# pwr_misc.net
KiCad netlist of a schematic drawn in Altium Designer
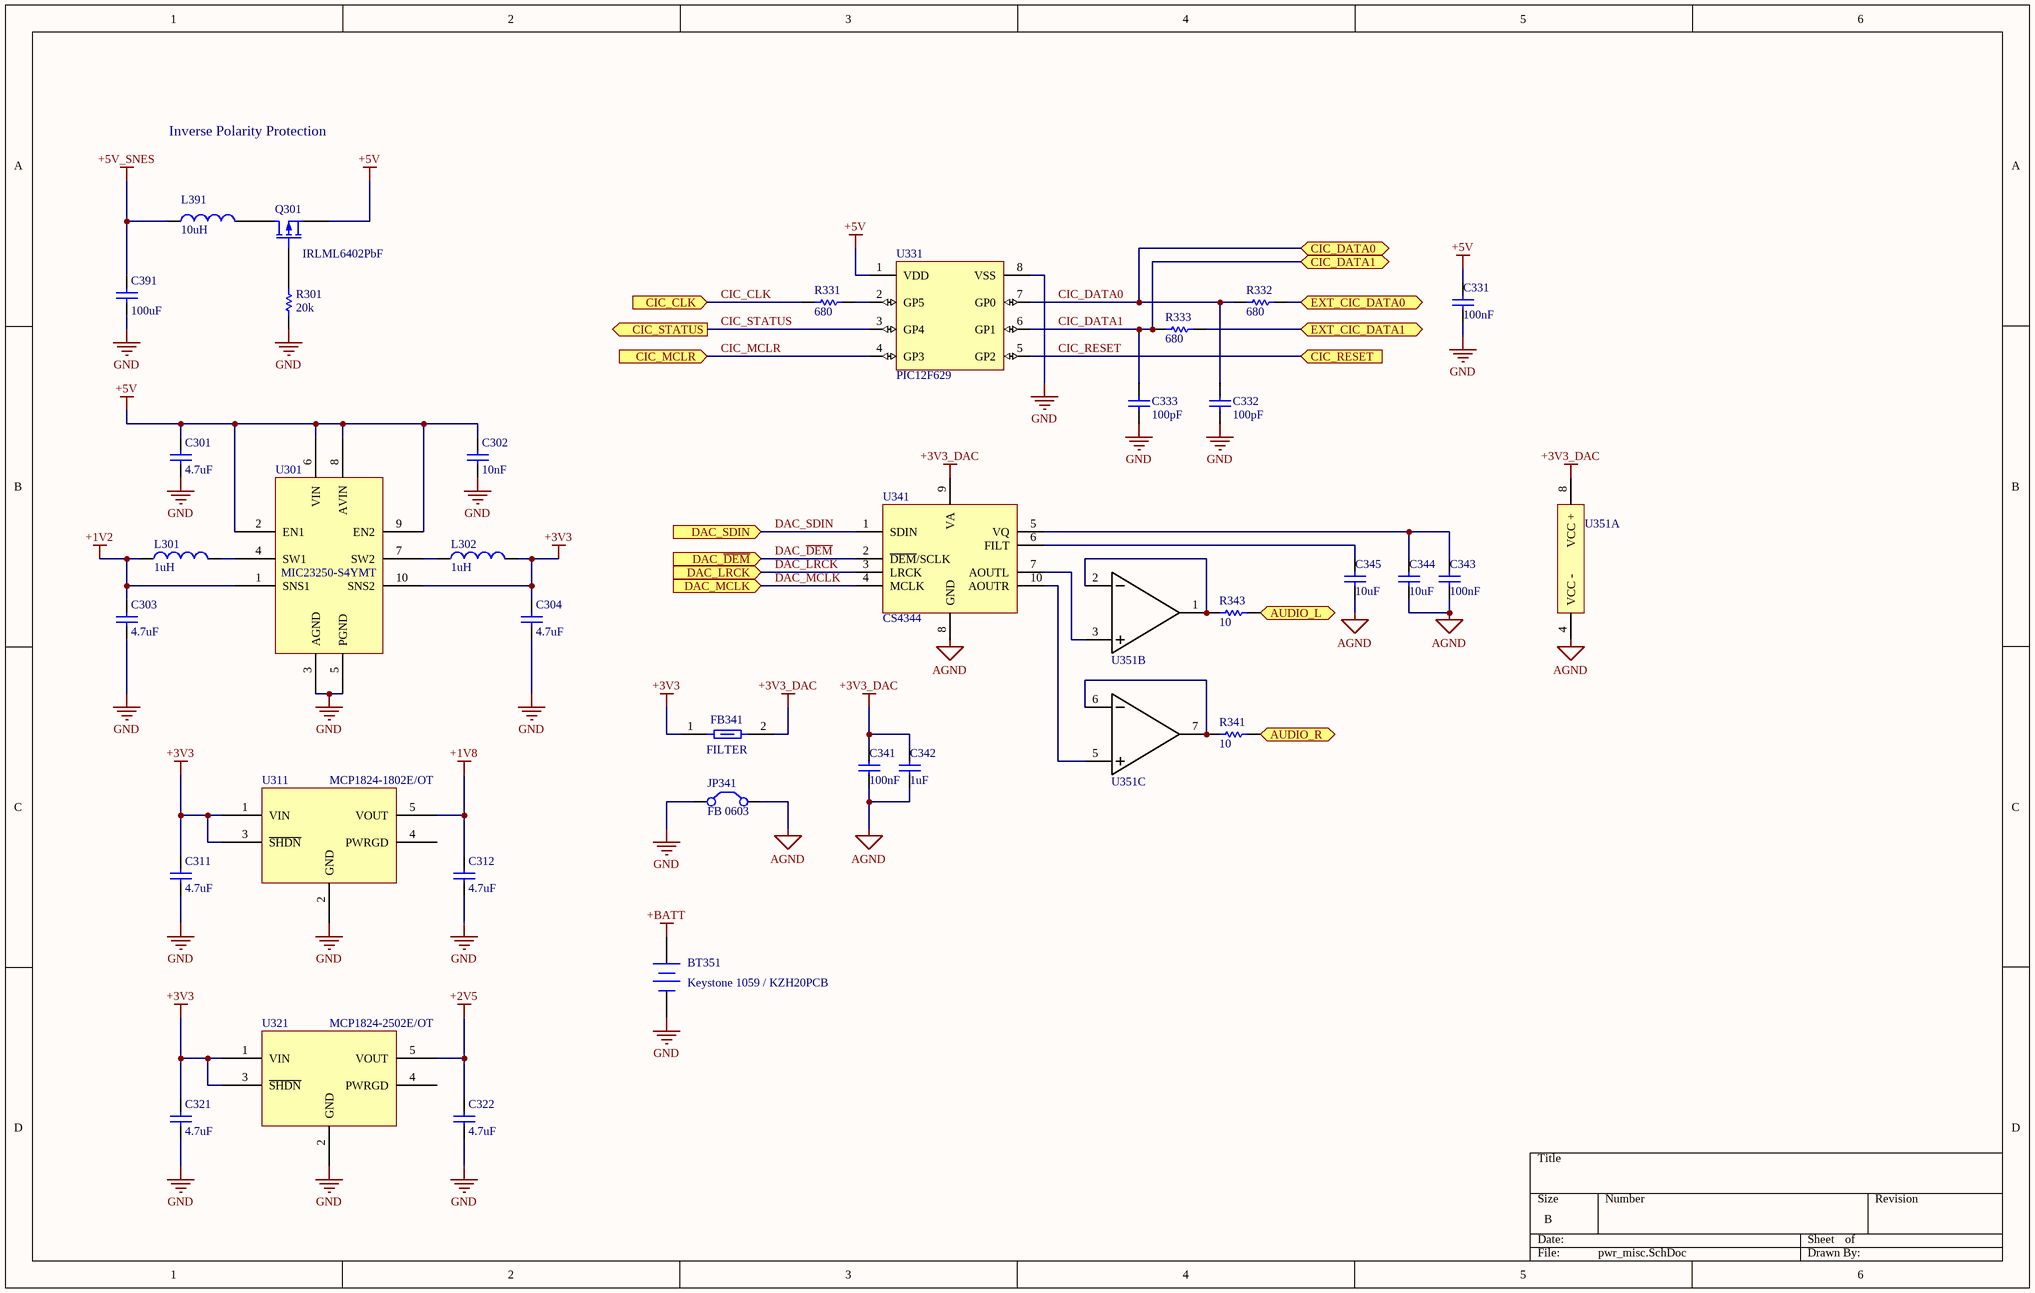
[diagram p0: pwr_misc.SchDoc]

(export (version "E")
  (design (tool "Eeschema 10.0.6"))
  (components
    (comp (ref "BT351")
      (value "Keystone 1059 / KZH20PCB")
      (footprint "BT_KEYSTONE_1059_20MM")
      (description "Battery")
      (libsource (lib "Miscellaneous Devices") (part "Battery"))
    )
    (comp (ref "C301")
      (value "4.7uF")
      (footprint "SM0805")
      (description "Capacitor")
      (libsource (lib "Miscellaneous Devices") (part "Cap"))
    )
    (comp (ref "C302")
      (value "10nF")
      (footprint "SM0805")
      (description "Capacitor")
      (libsource (lib "Miscellaneous Devices") (part "Cap"))
    )
    (comp (ref "C303")
      (value "4.7uF")
      (footprint "SM0805")
      (description "Capacitor")
      (libsource (lib "Miscellaneous Devices") (part "Cap"))
    )
    (comp (ref "C304")
      (value "4.7uF")
      (footprint "SM0805")
      (description "Capacitor")
      (libsource (lib "Miscellaneous Devices") (part "Cap"))
    )
    (comp (ref "C311")
      (value "4.7uF")
      (footprint "SM0805")
      (description "Capacitor")
      (libsource (lib "Miscellaneous Devices") (part "Cap"))
    )
    (comp (ref "C312")
      (value "4.7uF")
      (footprint "SM0805")
      (description "Capacitor")
      (libsource (lib "Miscellaneous Devices") (part "Cap"))
    )
    (comp (ref "C321")
      (value "4.7uF")
      (footprint "SM0805")
      (description "Capacitor")
      (libsource (lib "Miscellaneous Devices") (part "Cap"))
    )
    (comp (ref "C322")
      (value "4.7uF")
      (footprint "SM0805")
      (description "Capacitor")
      (libsource (lib "Miscellaneous Devices") (part "Cap"))
    )
    (comp (ref "C331")
      (value "100nF")
      (footprint "SM0805")
      (description "Capacitor")
      (libsource (lib "Miscellaneous Devices") (part "Cap"))
    )
    (comp (ref "C332")
      (value "100pF")
      (footprint "SM0805")
      (description "Capacitor")
      (libsource (lib "Miscellaneous Devices") (part "Cap"))
    )
    (comp (ref "C333")
      (value "100pF")
      (footprint "SM0805")
      (description "Capacitor")
      (libsource (lib "Miscellaneous Devices") (part "Cap"))
    )
    (comp (ref "C341")
      (value "100nF")
      (footprint "SM0805")
      (description "Capacitor")
      (libsource (lib "Miscellaneous Devices") (part "Cap"))
    )
    (comp (ref "C342")
      (value "1uF")
      (footprint "SM0805")
      (description "Capacitor")
      (libsource (lib "Miscellaneous Devices") (part "Cap"))
    )
    (comp (ref "C343")
      (value "100nF")
      (footprint "SM0805")
      (description "Capacitor")
      (libsource (lib "Miscellaneous Devices") (part "Cap"))
    )
    (comp (ref "C344")
      (value "10uF")
      (footprint "SM0805")
      (description "Capacitor")
      (libsource (lib "Miscellaneous Devices") (part "Cap"))
    )
    (comp (ref "C345")
      (value "10uF")
      (footprint "SM0805")
      (description "Capacitor")
      (libsource (lib "Miscellaneous Devices") (part "Cap"))
    )
    (comp (ref "C391")
      (value "100uF")
      (footprint "SM1210")
      (description "Capacitor")
      (libsource (lib "Miscellaneous Devices") (part "Cap"))
    )
    (comp (ref "FB341") (value "FILTER") (footprint "SM0805") (libsource (lib "Schlib1") (part "FILTER")))
    (comp (ref "JP341")
      (value "FB 0603")
      (footprint "JUMPER")
      (description "Jumper Wire")
      (libsource (lib "Miscellaneous Devices") (part "Jumper"))
    )
    (comp (ref "L301")
      (value "1uH")
      (footprint "SM1210L")
      (description "Inductor")
      (libsource (lib "Miscellaneous Devices") (part "Inductor"))
    )
    (comp (ref "L302")
      (value "1uH")
      (footprint "SM1210L")
      (description "Inductor")
      (libsource (lib "Miscellaneous Devices") (part "Inductor"))
    )
    (comp (ref "L391")
      (value "10uH")
      (footprint "SM1210L")
      (description "Inductor")
      (libsource (lib "Miscellaneous Devices") (part "Inductor"))
    )
    (comp (ref "Q301")
      (value "IRLML6402PbF")
      (footprint "SOT23DGS")
      (description "P-Channel MOSFET")
      (libsource (lib "Miscellaneous Devices") (part "MOSFET-P"))
    )
    (comp (ref "R301")
      (value "20k")
      (footprint "SM0805")
      (description "Resistor")
      (libsource (lib "Miscellaneous Devices") (part "Res1"))
    )
    (comp (ref "R331")
      (value "680")
      (footprint "SM0805")
      (description "Resistor")
      (libsource (lib "Miscellaneous Devices") (part "Res1"))
    )
    (comp (ref "R332")
      (value "680")
      (footprint "SM0805")
      (description "Resistor")
      (libsource (lib "Miscellaneous Devices") (part "Res1"))
    )
    (comp (ref "R333")
      (value "680")
      (footprint "SM0805")
      (description "Resistor")
      (libsource (lib "Miscellaneous Devices") (part "Res1"))
    )
    (comp (ref "R341")
      (value "10")
      (footprint "SM0805")
      (description "Resistor")
      (libsource (lib "Miscellaneous Devices") (part "Res1"))
    )
    (comp (ref "R343")
      (value "10")
      (footprint "SM0805")
      (description "Resistor")
      (libsource (lib "Miscellaneous Devices") (part "Res1"))
    )
    (comp (ref "U301")
      (value "MIC23250-S4YMT")
      (footprint "QFN10-2x2_LONGPADS")
      (libsource (lib "Schlib1") (part "MIC23250-S4YMT"))
    )
    (comp (ref "U311")
      (value "MCP1824-1802E/OT")
      (footprint "SOT23-5_LARGEPADS")
      (description "MCP1824")
      (libsource (lib "Schlib1") (part "MCP1824"))
    )
    (comp (ref "U321")
      (value "MCP1824-2502E/OT")
      (footprint "SOT23-5_LARGEPADS")
      (description "MCP1824")
      (libsource (lib "Schlib1") (part "MCP1824"))
    )
    (comp (ref "U331")
      (value "PIC12F629")
      (footprint "DIP-8__300")
      (libsource (lib "Schlib1") (part "PIC12F629"))
    )
    (comp (ref "U341") (value "CS4344") (footprint "TSSOP10") (libsource (lib "Schlib1") (part "CS4344")))
    (comp (ref "U351")
      (value "TS922")
      (footprint "SOIC127P600X175-8N")
      (libsource (lib "sd2snes") (part "TS922"))
    )
  )
  (nets
    (net (code "1") (name "+1V2") (class "Default")
      (node (ref "C303") (pin "1") (pinfunction "1_1") (pintype "passive"))
      (node (ref "L301") (pin "1") (pinfunction "1_1") (pintype "passive"))
      (node (ref "U301") (pin "1") (pinfunction "SNS1_1") (pintype "passive"))
    )
    (net (code "2") (name "+1V8") (class "Default")
      (node (ref "C312") (pin "1") (pinfunction "1_1") (pintype "passive"))
      (node (ref "U311") (pin "5") (pinfunction "VOUT_5") (pintype "passive"))
    )
    (net (code "3") (name "+2V5") (class "Default")
      (node (ref "C322") (pin "1") (pinfunction "1_1") (pintype "passive"))
      (node (ref "U321") (pin "5") (pinfunction "VOUT_5") (pintype "passive"))
    )
    (net (code "4") (name "+3V3") (class "Default")
      (node (ref "C304") (pin "1") (pinfunction "1_1") (pintype "passive"))
      (node (ref "C311") (pin "1") (pinfunction "1_1") (pintype "passive"))
      (node (ref "C321") (pin "1") (pinfunction "1_1") (pintype "passive"))
      (node (ref "FB341") (pin "1") (pinfunction "1_1") (pintype "passive"))
      (node (ref "L302") (pin "2") (pinfunction "2_2") (pintype "passive"))
      (node (ref "U301") (pin "10") (pinfunction "SNS2_10") (pintype "passive"))
      (node (ref "U311") (pin "1") (pinfunction "VIN_1") (pintype "passive"))
      (node (ref "U311") (pin "3") (pinfunction "~{SHDN}_3") (pintype "passive"))
      (node (ref "U321") (pin "1") (pinfunction "VIN_1") (pintype "passive"))
      (node (ref "U321") (pin "3") (pinfunction "~{SHDN}_3") (pintype "passive"))
    )
    (net (code "5") (name "+3V3_DAC") (class "Default")
      (node (ref "C341") (pin "1") (pinfunction "1_1") (pintype "passive"))
      (node (ref "C342") (pin "1") (pinfunction "1_1") (pintype "passive"))
      (node (ref "FB341") (pin "2") (pinfunction "2_2") (pintype "passive"))
      (node (ref "U341") (pin "9") (pinfunction "VA_9") (pintype "passive"))
      (node (ref "U351") (pin "8") (pinfunction "VCC_+_8") (pintype "power_in"))
    )
    (net (code "6") (name "+5V") (class "Default")
      (node (ref "C301") (pin "1") (pinfunction "1_1") (pintype "passive"))
      (node (ref "C302") (pin "1") (pinfunction "1_1") (pintype "passive"))
      (node (ref "C331") (pin "1") (pinfunction "1_1") (pintype "passive"))
      (node (ref "Q301") (pin "3") (pinfunction "S_3") (pintype "passive"))
      (node (ref "U301") (pin "2") (pinfunction "EN1_2") (pintype "passive"))
      (node (ref "U301") (pin "6") (pinfunction "VIN_6") (pintype "passive"))
      (node (ref "U301") (pin "8") (pinfunction "AVIN_8") (pintype "passive"))
      (node (ref "U301") (pin "9") (pinfunction "EN2_9") (pintype "passive"))
      (node (ref "U331") (pin "1") (pinfunction "VDD_1") (pintype "power_in"))
    )
    (net (code "7") (name "+5V_SNES") (class "Default")
      (node (ref "C391") (pin "1") (pinfunction "1_1") (pintype "passive"))
      (node (ref "L391") (pin "1") (pinfunction "1_1") (pintype "passive"))
    )
    (net (code "8") (name "+BATT") (class "Default")
      (node (ref "BT351") (pin "1") (pinfunction "+_1") (pintype "passive"))
    )
    (net (code "9") (name "/AUDIO_L") (class "Default")
      (node (ref "R343") (pin "1") (pinfunction "1_1") (pintype "passive"))
    )
    (net (code "10") (name "/AUDIO_R") (class "Default")
      (node (ref "R341") (pin "1") (pinfunction "1_1") (pintype "passive"))
    )
    (net (code "11") (name "/CIC_CLK") (class "Default")
      (node (ref "R331") (pin "2") (pinfunction "2_2") (pintype "passive"))
    )
    (net (code "12") (name "/CIC_DATA0") (class "Default")
      (node (ref "C332") (pin "1") (pinfunction "1_1") (pintype "passive"))
      (node (ref "R332") (pin "1") (pinfunction "1_1") (pintype "passive"))
      (node (ref "U331") (pin "7") (pinfunction "GP0_7") (pintype "bidirectional"))
    )
    (net (code "13") (name "/CIC_DATA1") (class "Default")
      (node (ref "C333") (pin "1") (pinfunction "1_1") (pintype "passive"))
      (node (ref "R333") (pin "2") (pinfunction "2_2") (pintype "passive"))
      (node (ref "U331") (pin "6") (pinfunction "GP1_6") (pintype "bidirectional"))
    )
    (net (code "14") (name "/CIC_MCLR") (class "Default")
      (node (ref "U331") (pin "4") (pinfunction "GP3_4") (pintype "bidirectional"))
    )
    (net (code "15") (name "/CIC_RESET") (class "Default")
      (node (ref "U331") (pin "5") (pinfunction "GP2_5") (pintype "bidirectional"))
    )
    (net (code "16") (name "/CIC_STATUS") (class "Default")
      (node (ref "U331") (pin "3") (pinfunction "GP4_3") (pintype "bidirectional"))
    )
    (net (code "17") (name "/DAC_LRCK") (class "Default")
      (node (ref "U341") (pin "3") (pinfunction "LRCK_3") (pintype "passive"))
    )
    (net (code "18") (name "/DAC_MCLK") (class "Default")
      (node (ref "U341") (pin "4") (pinfunction "MCLK_4") (pintype "passive"))
    )
    (net (code "19") (name "/DAC_SDIN") (class "Default")
      (node (ref "U341") (pin "1") (pinfunction "SDIN_1") (pintype "passive"))
    )
    (net (code "20") (name "/DAC_~{DEM}") (class "Default")
      (node (ref "U341") (pin "2") (pinfunction "~{DEM}/SCLK_2") (pintype "passive"))
    )
    (net (code "21") (name "/EXT_CIC_DATA0") (class "Default")
      (node (ref "R332") (pin "2") (pinfunction "2_2") (pintype "passive"))
    )
    (net (code "22") (name "/EXT_CIC_DATA1") (class "Default")
      (node (ref "R333") (pin "1") (pinfunction "1_1") (pintype "passive"))
    )
    (net (code "23") (name "AGND") (class "Default")
      (node (ref "C341") (pin "2") (pinfunction "2_2") (pintype "passive"))
      (node (ref "C342") (pin "2") (pinfunction "2_2") (pintype "passive"))
      (node (ref "C343") (pin "2") (pinfunction "2_2") (pintype "passive"))
      (node (ref "C344") (pin "2") (pinfunction "2_2") (pintype "passive"))
      (node (ref "C345") (pin "2") (pinfunction "2_2") (pintype "passive"))
      (node (ref "JP341") (pin "2") (pinfunction "C2_2") (pintype "passive"))
      (node (ref "U341") (pin "8") (pinfunction "GND_8") (pintype "passive"))
      (node (ref "U351") (pin "4") (pinfunction "VCC_-_4") (pintype "power_in"))
    )
    (net (code "24") (name "GND") (class "Default")
      (node (ref "BT351") (pin "2") (pinfunction "-_2") (pintype "passive"))
      (node (ref "C301") (pin "2") (pinfunction "2_2") (pintype "passive"))
      (node (ref "C302") (pin "2") (pinfunction "2_2") (pintype "passive"))
      (node (ref "C303") (pin "2") (pinfunction "2_2") (pintype "passive"))
      (node (ref "C304") (pin "2") (pinfunction "2_2") (pintype "passive"))
      (node (ref "C311") (pin "2") (pinfunction "2_2") (pintype "passive"))
      (node (ref "C312") (pin "2") (pinfunction "2_2") (pintype "passive"))
      (node (ref "C321") (pin "2") (pinfunction "2_2") (pintype "passive"))
      (node (ref "C322") (pin "2") (pinfunction "2_2") (pintype "passive"))
      (node (ref "C331") (pin "2") (pinfunction "2_2") (pintype "passive"))
      (node (ref "C332") (pin "2") (pinfunction "2_2") (pintype "passive"))
      (node (ref "C333") (pin "2") (pinfunction "2_2") (pintype "passive"))
      (node (ref "C391") (pin "2") (pinfunction "2_2") (pintype "passive"))
      (node (ref "JP341") (pin "1") (pinfunction "C1_1") (pintype "passive"))
      (node (ref "R301") (pin "1") (pinfunction "1_1") (pintype "passive"))
      (node (ref "U301") (pin "3") (pinfunction "AGND_3") (pintype "passive"))
      (node (ref "U301") (pin "5") (pinfunction "PGND_5") (pintype "passive"))
      (node (ref "U311") (pin "2") (pinfunction "GND_2") (pintype "passive"))
      (node (ref "U321") (pin "2") (pinfunction "GND_2") (pintype "passive"))
      (node (ref "U331") (pin "8") (pinfunction "VSS_8") (pintype "power_in"))
    )
    (net (code "25") (name "Net-(Q301-D)") (class "Default")
      (node (ref "L391") (pin "2") (pinfunction "2_2") (pintype "passive"))
      (node (ref "Q301") (pin "1") (pinfunction "D_1") (pintype "passive"))
    )
    (net (code "26") (name "Net-(Q301-G)") (class "Default")
      (node (ref "Q301") (pin "2") (pinfunction "G_2") (pintype "passive"))
      (node (ref "R301") (pin "2") (pinfunction "2_2") (pintype "passive"))
    )
    (net (code "27") (name "Net-(U301-SW1)") (class "Default")
      (node (ref "L301") (pin "2") (pinfunction "2_2") (pintype "passive"))
      (node (ref "U301") (pin "4") (pinfunction "SW1_4") (pintype "passive"))
    )
    (net (code "28") (name "Net-(U301-SW2)") (class "Default")
      (node (ref "L302") (pin "1") (pinfunction "1_1") (pintype "passive"))
      (node (ref "U301") (pin "7") (pinfunction "SW2_7") (pintype "passive"))
    )
    (net (code "29") (name "Net-(U331-GP5)") (class "Default")
      (node (ref "R331") (pin "1") (pinfunction "1_1") (pintype "passive"))
      (node (ref "U331") (pin "2") (pinfunction "GP5_2") (pintype "bidirectional"))
    )
    (net (code "30") (name "Net-(U341-AOUTL)") (class "Default")
      (node (ref "U341") (pin "7") (pinfunction "AOUTL_7") (pintype "passive"))
      (node (ref "U351") (pin "3") (pinfunction "IN1_+_3") (pintype "passive"))
    )
    (net (code "31") (name "Net-(U341-AOUTR)") (class "Default")
      (node (ref "U341") (pin "10") (pinfunction "AOUTR_10") (pintype "passive"))
      (node (ref "U351") (pin "5") (pinfunction "IN2_+_5") (pintype "passive"))
    )
    (net (code "32") (name "Net-(U341-FILT)") (class "Default")
      (node (ref "C345") (pin "1") (pinfunction "1_1") (pintype "passive"))
      (node (ref "U341") (pin "6") (pinfunction "FILT_6") (pintype "passive"))
    )
    (net (code "33") (name "Net-(U341-VQ)") (class "Default")
      (node (ref "C343") (pin "1") (pinfunction "1_1") (pintype "passive"))
      (node (ref "C344") (pin "1") (pinfunction "1_1") (pintype "passive"))
      (node (ref "U341") (pin "5") (pinfunction "VQ_5") (pintype "passive"))
    )
    (net (code "34") (name "Net-(U351B-IN1_-)") (class "Default")
      (node (ref "R343") (pin "2") (pinfunction "2_2") (pintype "passive"))
      (node (ref "U351") (pin "1") (pinfunction "OUT1_1") (pintype "passive"))
      (node (ref "U351") (pin "2") (pinfunction "IN1_-_2") (pintype "passive"))
    )
    (net (code "35") (name "Net-(U351C-IN2_-)") (class "Default")
      (node (ref "R341") (pin "2") (pinfunction "2_2") (pintype "passive"))
      (node (ref "U351") (pin "6") (pinfunction "IN2_-_6") (pintype "passive"))
      (node (ref "U351") (pin "7") (pinfunction "OUT2_7") (pintype "passive"))
    )
    (net (code "36") (name "unconnected-(U311-PWRGD-Pad4)") (class "Default")
      (node (ref "U311") (pin "4") (pinfunction "PWRGD_4") (pintype "passive"))
    )
    (net (code "37") (name "unconnected-(U321-PWRGD-Pad4)") (class "Default")
      (node (ref "U321") (pin "4") (pinfunction "PWRGD_4") (pintype "passive"))
    )
  )
)
